# output_elena.net
KiCad netlist of a schematic drawn in EAGLE
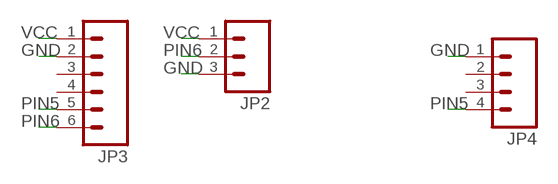
[diagram p0: schematic, sheet 1]

(export (version "E")
  (design (tool "Eeschema 10.0.6"))
  (components
    (comp (ref "JP2")
      (value "M031X03_NO_SILK")
      (footprint "eagle-import:1X03_NO_SILK")
      (libsource (lib "eagle-import") (part "M031X03_NO_SILK"))
    )
    (comp (ref "JP3")
      (value "M06LONGPADS")
      (footprint "eagle-import:1X06_LONGPADS")
      (libsource (lib "eagle-import") (part "M06LONGPADS"))
    )
    (comp (ref "JP4")
      (value "M04LONGPADS")
      (footprint "eagle-import:1X04_LONGPADS")
      (libsource (lib "eagle-import") (part "M04LONGPADS"))
    )
  )
  (nets
    (net (code "1") (name "/GND") (class "Default")
      (node (ref "JP2") (pin "3") (pinfunction "3_3") (pintype "passive"))
      (node (ref "JP3") (pin "2") (pinfunction "2_2") (pintype "passive"))
      (node (ref "JP4") (pin "1") (pinfunction "1_1") (pintype "passive"))
    )
    (net (code "2") (name "/PIN5") (class "Default")
      (node (ref "JP3") (pin "5") (pinfunction "5_5") (pintype "passive"))
      (node (ref "JP4") (pin "4") (pinfunction "4_4") (pintype "passive"))
    )
    (net (code "3") (name "/PIN6") (class "Default")
      (node (ref "JP2") (pin "2") (pinfunction "2_2") (pintype "passive"))
      (node (ref "JP3") (pin "6") (pinfunction "6_6") (pintype "passive"))
    )
    (net (code "4") (name "/VCC") (class "Default")
      (node (ref "JP2") (pin "1") (pinfunction "1_1") (pintype "passive"))
      (node (ref "JP3") (pin "1") (pinfunction "1_1") (pintype "passive"))
    )
    (net (code "5") (name "unconnected-(JP3-Pad3)") (class "Default")
      (node (ref "JP3") (pin "3") (pinfunction "3_3") (pintype "passive"))
    )
    (net (code "6") (name "unconnected-(JP3-Pad4)") (class "Default")
      (node (ref "JP3") (pin "4") (pinfunction "4_4") (pintype "passive"))
    )
    (net (code "7") (name "unconnected-(JP4-Pad2)") (class "Default")
      (node (ref "JP4") (pin "2") (pinfunction "2_2") (pintype "passive"))
    )
    (net (code "8") (name "unconnected-(JP4-Pad3)") (class "Default")
      (node (ref "JP4") (pin "3") (pinfunction "3_3") (pintype "passive"))
    )
  )
)
